# mv-uart.net
KiCad netlist of a schematic drawn in EAGLE
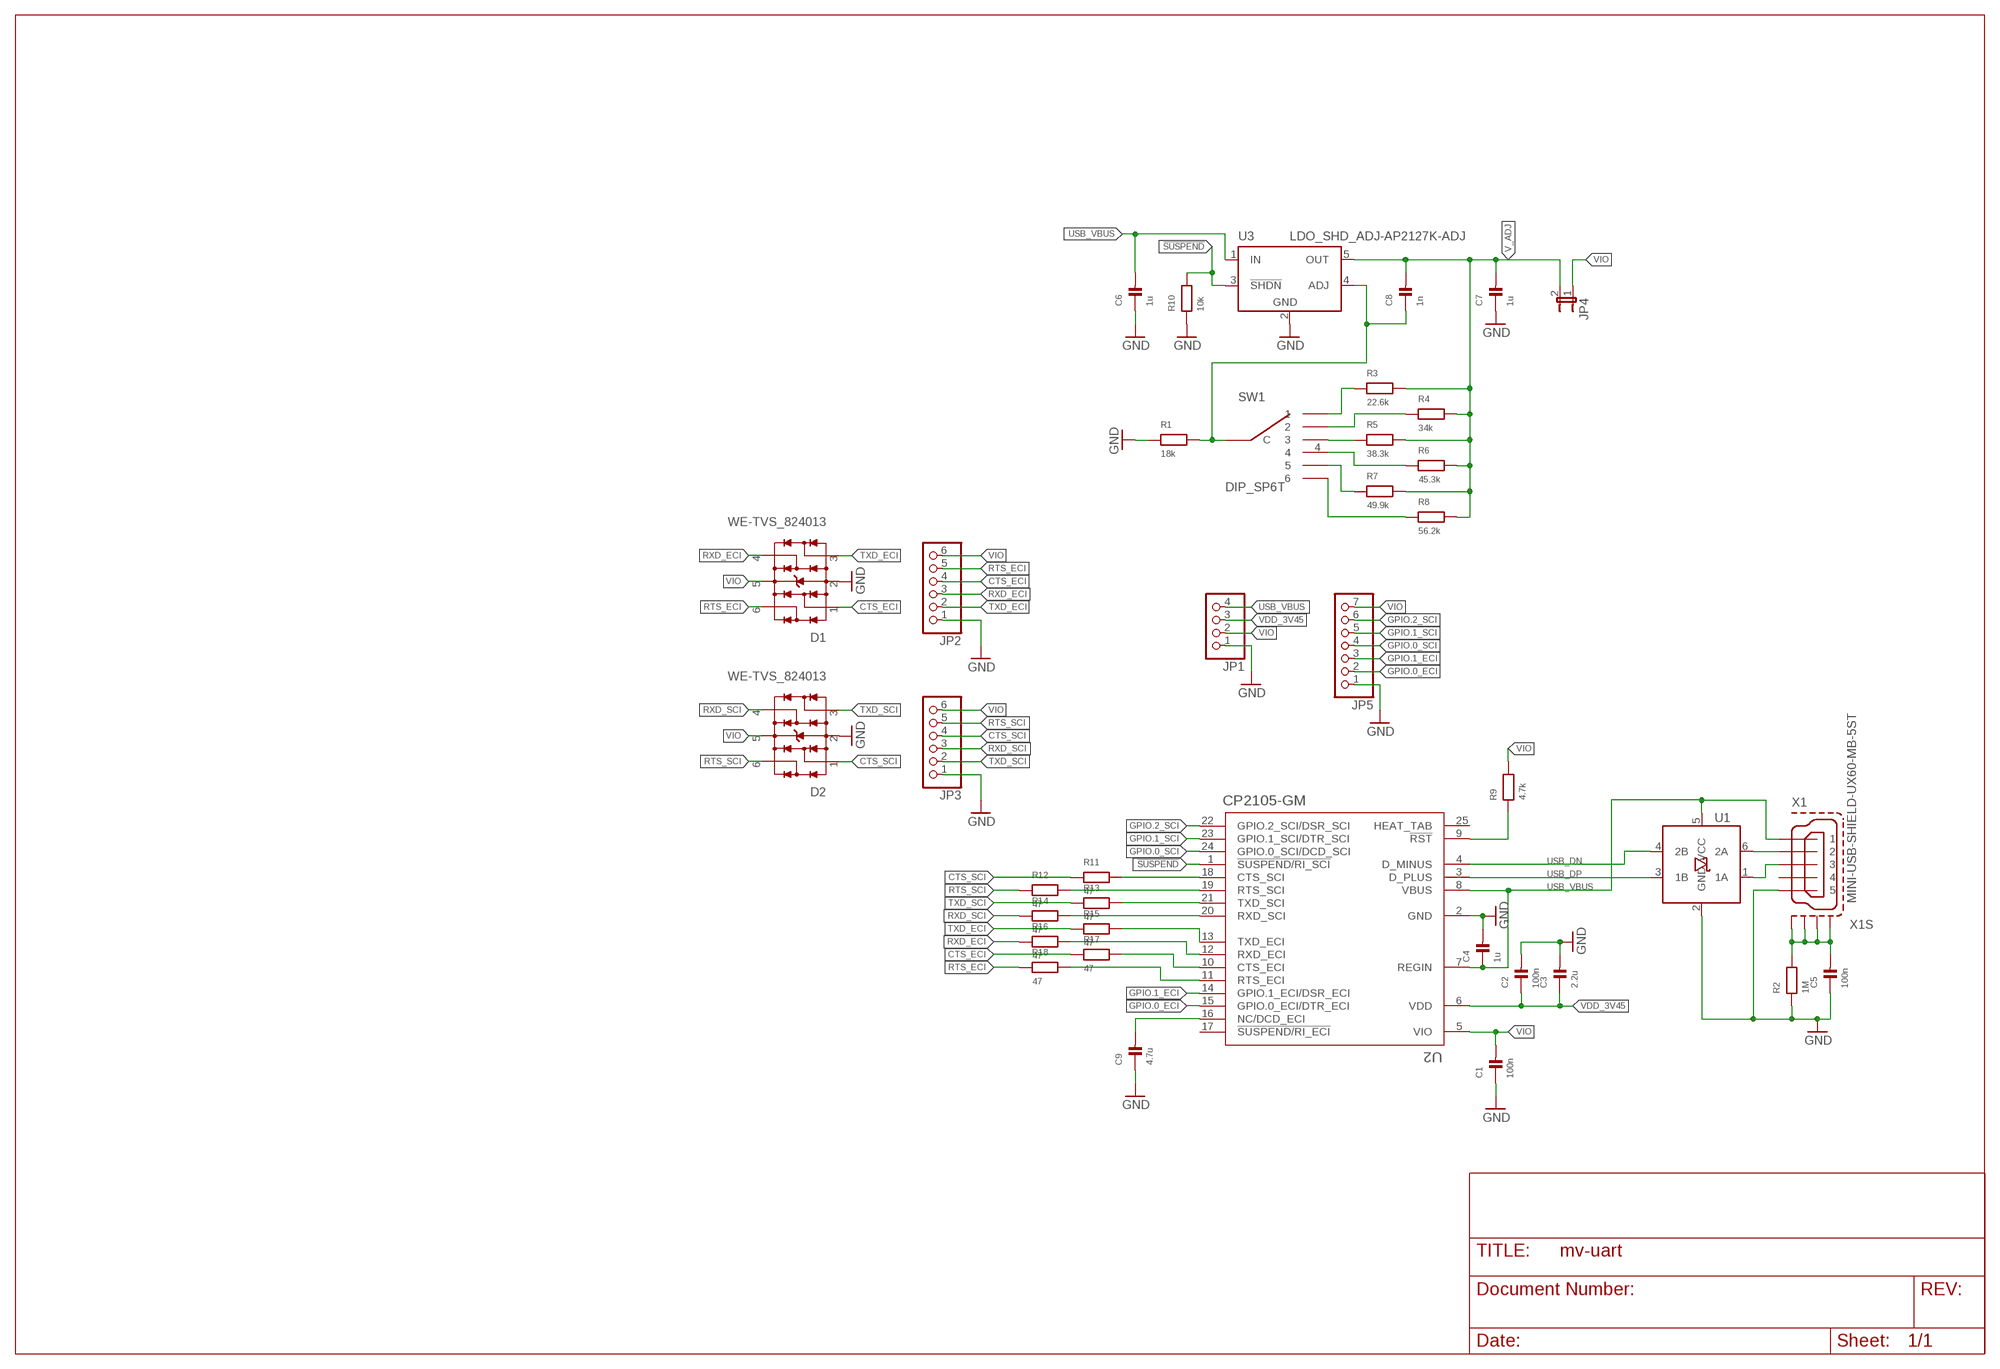
[diagram p0: schematic, sheet 1]

(export (version "E")
  (design (tool "Eeschema 10.0.6"))
  (components
    (comp (ref "C1")
      (value "100n")
      (footprint "eagle-import:_0603")
      (libsource (lib "eagle-import") (part "CAP_CERAMIC_0603"))
    )
    (comp (ref "C2")
      (value "100n")
      (footprint "eagle-import:_0603")
      (libsource (lib "eagle-import") (part "CAP_CERAMIC_0603"))
    )
    (comp (ref "C3")
      (value "2.2u")
      (footprint "eagle-import:_0603")
      (libsource (lib "eagle-import") (part "CAP_CERAMIC_0603"))
    )
    (comp (ref "C4")
      (value "1u")
      (footprint "eagle-import:_0603")
      (libsource (lib "eagle-import") (part "CAP_CERAMIC_0603"))
    )
    (comp (ref "C5")
      (value "100n")
      (footprint "eagle-import:_0603")
      (libsource (lib "eagle-import") (part "CAP_CERAMIC_0603"))
    )
    (comp (ref "C6")
      (value "1u")
      (footprint "eagle-import:_0603")
      (libsource (lib "eagle-import") (part "CAP_CERAMIC_0603"))
    )
    (comp (ref "C7")
      (value "1u")
      (footprint "eagle-import:_0603")
      (libsource (lib "eagle-import") (part "CAP_CERAMIC_0603"))
    )
    (comp (ref "C8")
      (value "1n")
      (footprint "eagle-import:_0603")
      (libsource (lib "eagle-import") (part "CAP_CERAMIC_0603"))
    )
    (comp (ref "C9")
      (value "4.7u")
      (footprint "eagle-import:_0603")
      (libsource (lib "eagle-import") (part "CAP_CERAMIC_0603"))
    )
    (comp (ref "D1")
      (value "WE-TVS_824013")
      (footprint "eagle-import:WE-TVS_SOT23-6L")
      (libsource (lib "eagle-import") (part "WE-TVS_824013"))
    )
    (comp (ref "D2")
      (value "WE-TVS_824013")
      (footprint "eagle-import:WE-TVS_SOT23-6L")
      (libsource (lib "eagle-import") (part "WE-TVS_824013"))
    )
    (comp (ref "JP1")
      (value "PINHD-1X4")
      (footprint "eagle-import:1X04")
      (libsource (lib "eagle-import") (part "PINHD-1X4"))
    )
    (comp (ref "JP2")
      (value "PINHD-1X6/90")
      (footprint "eagle-import:1X06_90")
      (libsource (lib "eagle-import") (part "PINHD-1X6/90"))
    )
    (comp (ref "JP3")
      (value "PINHD-1X6/90")
      (footprint "eagle-import:1X06_90")
      (libsource (lib "eagle-import") (part "PINHD-1X6/90"))
    )
    (comp (ref "JP4")
      (value "JP1E")
      (footprint "eagle-import:JP1")
      (libsource (lib "eagle-import") (part "JP1E"))
    )
    (comp (ref "JP5")
      (value "PINHD-1X7")
      (footprint "eagle-import:1X07")
      (libsource (lib "eagle-import") (part "PINHD-1X7"))
    )
    (comp (ref "R1")
      (value "18k")
      (footprint "eagle-import:_0603")
      (libsource (lib "eagle-import") (part "RESISTOR_0603"))
    )
    (comp (ref "R2")
      (value "1M")
      (footprint "eagle-import:_0603")
      (libsource (lib "eagle-import") (part "RESISTOR_0603"))
    )
    (comp (ref "R3")
      (value "22.6k")
      (footprint "eagle-import:_0603")
      (libsource (lib "eagle-import") (part "RESISTOR_0603"))
    )
    (comp (ref "R4")
      (value "34k")
      (footprint "eagle-import:_0603")
      (libsource (lib "eagle-import") (part "RESISTOR_0603"))
    )
    (comp (ref "R5")
      (value "38.3k")
      (footprint "eagle-import:_0603")
      (libsource (lib "eagle-import") (part "RESISTOR_0603"))
    )
    (comp (ref "R6")
      (value "45.3k")
      (footprint "eagle-import:_0603")
      (libsource (lib "eagle-import") (part "RESISTOR_0603"))
    )
    (comp (ref "R7")
      (value "49.9k")
      (footprint "eagle-import:_0603")
      (libsource (lib "eagle-import") (part "RESISTOR_0603"))
    )
    (comp (ref "R8")
      (value "56.2k")
      (footprint "eagle-import:_0603")
      (libsource (lib "eagle-import") (part "RESISTOR_0603"))
    )
    (comp (ref "R9")
      (value "4.7k")
      (footprint "eagle-import:_0603")
      (libsource (lib "eagle-import") (part "RESISTOR_0603"))
    )
    (comp (ref "R10")
      (value "10k")
      (footprint "eagle-import:_0603")
      (libsource (lib "eagle-import") (part "RESISTOR_0603"))
    )
    (comp (ref "R11")
      (value "47")
      (footprint "eagle-import:_0603")
      (libsource (lib "eagle-import") (part "RESISTOR_0603"))
    )
    (comp (ref "R12")
      (value "47")
      (footprint "eagle-import:_0603")
      (libsource (lib "eagle-import") (part "RESISTOR_0603"))
    )
    (comp (ref "R13")
      (value "47")
      (footprint "eagle-import:_0603")
      (libsource (lib "eagle-import") (part "RESISTOR_0603"))
    )
    (comp (ref "R14")
      (value "47")
      (footprint "eagle-import:_0603")
      (libsource (lib "eagle-import") (part "RESISTOR_0603"))
    )
    (comp (ref "R15")
      (value "47")
      (footprint "eagle-import:_0603")
      (libsource (lib "eagle-import") (part "RESISTOR_0603"))
    )
    (comp (ref "R16")
      (value "47")
      (footprint "eagle-import:_0603")
      (libsource (lib "eagle-import") (part "RESISTOR_0603"))
    )
    (comp (ref "R17")
      (value "47")
      (footprint "eagle-import:_0603")
      (libsource (lib "eagle-import") (part "RESISTOR_0603"))
    )
    (comp (ref "R18")
      (value "47")
      (footprint "eagle-import:_0603")
      (libsource (lib "eagle-import") (part "RESISTOR_0603"))
    )
    (comp (ref "SW1")
      (value "DIP_SP6T")
      (footprint "eagle-import:DIP_SP6T")
      (libsource (lib "eagle-import") (part "DIP_SP6T"))
    )
    (comp (ref "U1")
      (value "IP4234CZ6")
      (footprint "eagle-import:TSOP-6")
      (libsource (lib "eagle-import") (part "IP4234CZ6"))
    )
    (comp (ref "U2")
      (value "CP2105-GM")
      (footprint "eagle-import:QFN24_4X4")
      (libsource (lib "eagle-import") (part "CP2105-GM"))
    )
    (comp (ref "U3")
      (value "LDO_SHD_ADJ-AP2127K-ADJ")
      (footprint "eagle-import:SOT23L")
      (libsource (lib "eagle-import") (part "LDO_SHD_ADJ-AP2127K-ADJ"))
    )
    (comp (ref "X1")
      (value "MINI-USB-SHIELD-UX60-MB-5ST")
      (footprint "eagle-import:UX60-MB-5ST")
      (libsource (lib "eagle-import") (part "MINI-USB-SHIELD-UX60-MB-5ST"))
    )
  )
  (nets
    (net (code "1") (name "/USB_DN") (class "Default")
      (node (ref "U1") (pin "4") (pinfunction "2B_4") (pintype "passive"))
      (node (ref "U2") (pin "4") (pinfunction "D_MINUS_4") (pintype "passive"))
    )
    (net (code "2") (name "/USB_DP") (class "Default")
      (node (ref "U1") (pin "3") (pinfunction "1B_3") (pintype "passive"))
      (node (ref "U2") (pin "3") (pinfunction "D_PLUS_3") (pintype "passive"))
    )
    (net (code "3") (name "/~{SUSPEND}") (class "Default")
      (node (ref "R10") (pin "2") (pinfunction "2_2") (pintype "passive"))
      (node (ref "U2") (pin "1") (pinfunction "~{SUSPEND/RI_SCI}_1") (pintype "passive"))
      (node (ref "U3") (pin "3") (pinfunction "~{SHDN}_3") (pintype "input"))
    )
    (net (code "4") (name "CTS_ECI") (class "Default")
      (node (ref "D1") (pin "1") (pinfunction "1_1") (pintype "passive"))
      (node (ref "JP2") (pin "4") (pinfunction "4_4") (pintype "passive"))
      (node (ref "R17") (pin "1") (pinfunction "1_1") (pintype "passive"))
    )
    (net (code "5") (name "CTS_SCI") (class "Default")
      (node (ref "D2") (pin "1") (pinfunction "1_1") (pintype "passive"))
      (node (ref "JP3") (pin "4") (pinfunction "4_4") (pintype "passive"))
      (node (ref "R11") (pin "1") (pinfunction "1_1") (pintype "passive"))
    )
    (net (code "6") (name "GND") (class "Default")
      (node (ref "C1") (pin "1") (pinfunction "1_1") (pintype "passive"))
      (node (ref "C2") (pin "2") (pinfunction "2_2") (pintype "passive"))
      (node (ref "C3") (pin "2") (pinfunction "2_2") (pintype "passive"))
      (node (ref "C4") (pin "2") (pinfunction "2_2") (pintype "passive"))
      (node (ref "C5") (pin "1") (pinfunction "1_1") (pintype "passive"))
      (node (ref "C6") (pin "1") (pinfunction "1_1") (pintype "passive"))
      (node (ref "C7") (pin "1") (pinfunction "1_1") (pintype "passive"))
      (node (ref "C9") (pin "1") (pinfunction "1_1") (pintype "passive"))
      (node (ref "D1") (pin "2") (pinfunction "GND_2") (pintype "power_in"))
      (node (ref "D2") (pin "2") (pinfunction "GND_2") (pintype "power_in"))
      (node (ref "JP1") (pin "1") (pinfunction "1_1") (pintype "passive"))
      (node (ref "JP2") (pin "1") (pinfunction "1_1") (pintype "passive"))
      (node (ref "JP3") (pin "1") (pinfunction "1_1") (pintype "passive"))
      (node (ref "JP5") (pin "1") (pinfunction "1_1") (pintype "passive"))
      (node (ref "R1") (pin "1") (pinfunction "1_1") (pintype "passive"))
      (node (ref "R10") (pin "1") (pinfunction "1_1") (pintype "passive"))
      (node (ref "R2") (pin "1") (pinfunction "1_1") (pintype "passive"))
      (node (ref "U1") (pin "2") (pinfunction "GND_2") (pintype "passive"))
      (node (ref "U2") (pin "2") (pinfunction "GND_2") (pintype "power_in"))
      (node (ref "U3") (pin "2") (pinfunction "GND_2") (pintype "power_in"))
      (node (ref "X1") (pin "5") (pinfunction "5_5") (pintype "input"))
    )
    (net (code "7") (name "GPIO.0_ECI") (class "Default")
      (node (ref "JP5") (pin "2") (pinfunction "2_2") (pintype "passive"))
      (node (ref "U2") (pin "15") (pinfunction "GPIO.0_ECI/DTR_ECI_15") (pintype "passive"))
    )
    (net (code "8") (name "GPIO.0_SCI") (class "Default")
      (node (ref "JP5") (pin "4") (pinfunction "4_4") (pintype "passive"))
      (node (ref "U2") (pin "24") (pinfunction "GPIO.0_SCI/DCD_SCI_24") (pintype "passive"))
    )
    (net (code "9") (name "GPIO.1_ECI") (class "Default")
      (node (ref "JP5") (pin "3") (pinfunction "3_3") (pintype "passive"))
      (node (ref "U2") (pin "14") (pinfunction "GPIO.1_ECI/DSR_ECI_14") (pintype "passive"))
    )
    (net (code "10") (name "GPIO.1_SCI") (class "Default")
      (node (ref "JP5") (pin "5") (pinfunction "5_5") (pintype "passive"))
      (node (ref "U2") (pin "23") (pinfunction "GPIO.1_SCI/DTR_SCI_23") (pintype "passive"))
    )
    (net (code "11") (name "GPIO.2_SCI") (class "Default")
      (node (ref "JP5") (pin "6") (pinfunction "6_6") (pintype "passive"))
      (node (ref "U2") (pin "22") (pinfunction "GPIO.2_SCI/DSR_SCI_22") (pintype "passive"))
    )
    (net (code "12") (name "Net-(R3-Pad1)") (class "Default")
      (node (ref "R3") (pin "1") (pinfunction "1_1") (pintype "passive"))
      (node (ref "SW1") (pin "1") (pinfunction "1_1") (pintype "bidirectional"))
    )
    (net (code "13") (name "Net-(R4-Pad1)") (class "Default")
      (node (ref "R4") (pin "1") (pinfunction "1_1") (pintype "passive"))
      (node (ref "SW1") (pin "2") (pinfunction "2_2") (pintype "bidirectional"))
    )
    (net (code "14") (name "Net-(R5-Pad1)") (class "Default")
      (node (ref "R5") (pin "1") (pinfunction "1_1") (pintype "passive"))
      (node (ref "SW1") (pin "3") (pinfunction "3_3") (pintype "bidirectional"))
    )
    (net (code "15") (name "Net-(R6-Pad1)") (class "Default")
      (node (ref "R6") (pin "1") (pinfunction "1_1") (pintype "passive"))
      (node (ref "SW1") (pin "4") (pinfunction "4_4") (pintype "bidirectional"))
    )
    (net (code "16") (name "Net-(R7-Pad1)") (class "Default")
      (node (ref "R7") (pin "1") (pinfunction "1_1") (pintype "passive"))
      (node (ref "SW1") (pin "5") (pinfunction "5_5") (pintype "bidirectional"))
    )
    (net (code "17") (name "Net-(R8-Pad1)") (class "Default")
      (node (ref "R8") (pin "1") (pinfunction "1_1") (pintype "passive"))
      (node (ref "SW1") (pin "6") (pinfunction "6_6") (pintype "bidirectional"))
    )
    (net (code "18") (name "Net-(U1-1A)") (class "Default")
      (node (ref "U1") (pin "1") (pinfunction "1A_1") (pintype "passive"))
      (node (ref "X1") (pin "3") (pinfunction "3_3") (pintype "input"))
    )
    (net (code "19") (name "Net-(U1-2A)") (class "Default")
      (node (ref "U1") (pin "6") (pinfunction "2A_6") (pintype "passive"))
      (node (ref "X1") (pin "2") (pinfunction "2_2") (pintype "input"))
    )
    (net (code "20") (name "Net-(U2-CTS_ECI)") (class "Default")
      (node (ref "R17") (pin "2") (pinfunction "2_2") (pintype "passive"))
      (node (ref "U2") (pin "10") (pinfunction "CTS_ECI_10") (pintype "passive"))
    )
    (net (code "21") (name "Net-(U2-CTS_SCI)") (class "Default")
      (node (ref "R11") (pin "2") (pinfunction "2_2") (pintype "passive"))
      (node (ref "U2") (pin "18") (pinfunction "CTS_SCI_18") (pintype "passive"))
    )
    (net (code "22") (name "Net-(U2-NC{slash}DCD_ECI)") (class "Default")
      (node (ref "C9") (pin "2") (pinfunction "2_2") (pintype "passive"))
      (node (ref "U2") (pin "16") (pinfunction "NC/DCD_ECI_16") (pintype "passive"))
    )
    (net (code "23") (name "Net-(U2-RTS_ECI)") (class "Default")
      (node (ref "R18") (pin "2") (pinfunction "2_2") (pintype "passive"))
      (node (ref "U2") (pin "11") (pinfunction "RTS_ECI_11") (pintype "passive"))
    )
    (net (code "24") (name "Net-(U2-RTS_SCI)") (class "Default")
      (node (ref "R12") (pin "2") (pinfunction "2_2") (pintype "passive"))
      (node (ref "U2") (pin "19") (pinfunction "RTS_SCI_19") (pintype "passive"))
    )
    (net (code "25") (name "Net-(U2-RXD_ECI)") (class "Default")
      (node (ref "R16") (pin "2") (pinfunction "2_2") (pintype "passive"))
      (node (ref "U2") (pin "12") (pinfunction "RXD_ECI_12") (pintype "passive"))
    )
    (net (code "26") (name "Net-(U2-RXD_SCI)") (class "Default")
      (node (ref "R14") (pin "2") (pinfunction "2_2") (pintype "passive"))
      (node (ref "U2") (pin "20") (pinfunction "RXD_SCI_20") (pintype "passive"))
    )
    (net (code "27") (name "Net-(U2-TXD_ECI)") (class "Default")
      (node (ref "R15") (pin "2") (pinfunction "2_2") (pintype "passive"))
      (node (ref "U2") (pin "13") (pinfunction "TXD_ECI_13") (pintype "passive"))
    )
    (net (code "28") (name "Net-(U2-TXD_SCI)") (class "Default")
      (node (ref "R13") (pin "2") (pinfunction "2_2") (pintype "passive"))
      (node (ref "U2") (pin "21") (pinfunction "TXD_SCI_21") (pintype "passive"))
    )
    (net (code "29") (name "Net-(U2-~{RST})") (class "Default")
      (node (ref "R9") (pin "1") (pinfunction "1_1") (pintype "passive"))
      (node (ref "U2") (pin "9") (pinfunction "~{RST}_9") (pintype "passive"))
    )
    (net (code "30") (name "Net-(U3-ADJ)") (class "Default")
      (node (ref "C8") (pin "1") (pinfunction "1_1") (pintype "passive"))
      (node (ref "R1") (pin "2") (pinfunction "2_2") (pintype "passive"))
      (node (ref "SW1") (pin "C") (pinfunction "C_C") (pintype "bidirectional"))
      (node (ref "U3") (pin "4") (pinfunction "ADJ_4") (pintype "passive"))
    )
    (net (code "31") (name "Net-(X1B-S1)") (class "Default")
      (node (ref "C5") (pin "2") (pinfunction "2_2") (pintype "passive"))
      (node (ref "R2") (pin "2") (pinfunction "2_2") (pintype "passive"))
      (node (ref "X1") (pin "M1") (pinfunction "S1_M1") (pintype "passive"))
      (node (ref "X1") (pin "M2") (pinfunction "S2_M2") (pintype "passive"))
      (node (ref "X1") (pin "M3") (pinfunction "S3_M3") (pintype "passive"))
      (node (ref "X1") (pin "M4") (pinfunction "S4_M4") (pintype "passive"))
    )
    (net (code "32") (name "RTS_ECI") (class "Default")
      (node (ref "D1") (pin "6") (pinfunction "4_6") (pintype "passive"))
      (node (ref "JP2") (pin "5") (pinfunction "5_5") (pintype "passive"))
      (node (ref "R18") (pin "1") (pinfunction "1_1") (pintype "passive"))
    )
    (net (code "33") (name "RTS_SCI") (class "Default")
      (node (ref "D2") (pin "6") (pinfunction "4_6") (pintype "passive"))
      (node (ref "JP3") (pin "5") (pinfunction "5_5") (pintype "passive"))
      (node (ref "R12") (pin "1") (pinfunction "1_1") (pintype "passive"))
    )
    (net (code "34") (name "RXD_ECI") (class "Default")
      (node (ref "D1") (pin "4") (pinfunction "3_4") (pintype "passive"))
      (node (ref "JP2") (pin "3") (pinfunction "3_3") (pintype "passive"))
      (node (ref "R16") (pin "1") (pinfunction "1_1") (pintype "passive"))
    )
    (net (code "35") (name "RXD_SCI") (class "Default")
      (node (ref "D2") (pin "4") (pinfunction "3_4") (pintype "passive"))
      (node (ref "JP3") (pin "3") (pinfunction "3_3") (pintype "passive"))
      (node (ref "R14") (pin "1") (pinfunction "1_1") (pintype "passive"))
    )
    (net (code "36") (name "TXD_ECI") (class "Default")
      (node (ref "D1") (pin "3") (pinfunction "2_3") (pintype "passive"))
      (node (ref "JP2") (pin "2") (pinfunction "2_2") (pintype "passive"))
      (node (ref "R15") (pin "1") (pinfunction "1_1") (pintype "passive"))
    )
    (net (code "37") (name "TXD_SCI") (class "Default")
      (node (ref "D2") (pin "3") (pinfunction "2_3") (pintype "passive"))
      (node (ref "JP3") (pin "2") (pinfunction "2_2") (pintype "passive"))
      (node (ref "R13") (pin "1") (pinfunction "1_1") (pintype "passive"))
    )
    (net (code "38") (name "USB_VBUS") (class "Default")
      (node (ref "C4") (pin "1") (pinfunction "1_1") (pintype "passive"))
      (node (ref "C6") (pin "2") (pinfunction "2_2") (pintype "passive"))
      (node (ref "JP1") (pin "4") (pinfunction "4_4") (pintype "passive"))
      (node (ref "U1") (pin "5") (pinfunction "VCC_5") (pintype "passive"))
      (node (ref "U2") (pin "7") (pinfunction "REGIN_7") (pintype "input"))
      (node (ref "U2") (pin "8") (pinfunction "VBUS_8") (pintype "input"))
      (node (ref "U3") (pin "1") (pinfunction "IN_1") (pintype "input"))
      (node (ref "X1") (pin "1") (pinfunction "1_1") (pintype "input"))
    )
    (net (code "39") (name "VDD_3V45") (class "Default")
      (node (ref "C2") (pin "1") (pinfunction "1_1") (pintype "passive"))
      (node (ref "C3") (pin "1") (pinfunction "1_1") (pintype "passive"))
      (node (ref "JP1") (pin "3") (pinfunction "3_3") (pintype "passive"))
      (node (ref "U2") (pin "6") (pinfunction "VDD_6") (pintype "power_in"))
    )
    (net (code "40") (name "VIO") (class "Default")
      (node (ref "C1") (pin "2") (pinfunction "2_2") (pintype "passive"))
      (node (ref "D1") (pin "5") (pinfunction "VDD_5") (pintype "power_in"))
      (node (ref "D2") (pin "5") (pinfunction "VDD_5") (pintype "power_in"))
      (node (ref "JP1") (pin "2") (pinfunction "2_2") (pintype "passive"))
      (node (ref "JP2") (pin "6") (pinfunction "6_6") (pintype "passive"))
      (node (ref "JP3") (pin "6") (pinfunction "6_6") (pintype "passive"))
      (node (ref "JP4") (pin "1") (pinfunction "1_1") (pintype "passive"))
      (node (ref "JP5") (pin "7") (pinfunction "7_7") (pintype "passive"))
      (node (ref "R9") (pin "2") (pinfunction "2_2") (pintype "passive"))
      (node (ref "U2") (pin "5") (pinfunction "VIO_5") (pintype "power_in"))
    )
    (net (code "41") (name "V_ADJ") (class "Default")
      (node (ref "C7") (pin "2") (pinfunction "2_2") (pintype "passive"))
      (node (ref "C8") (pin "2") (pinfunction "2_2") (pintype "passive"))
      (node (ref "JP4") (pin "2") (pinfunction "2_2") (pintype "passive"))
      (node (ref "R3") (pin "2") (pinfunction "2_2") (pintype "passive"))
      (node (ref "R4") (pin "2") (pinfunction "2_2") (pintype "passive"))
      (node (ref "R5") (pin "2") (pinfunction "2_2") (pintype "passive"))
      (node (ref "R6") (pin "2") (pinfunction "2_2") (pintype "passive"))
      (node (ref "R7") (pin "2") (pinfunction "2_2") (pintype "passive"))
      (node (ref "R8") (pin "2") (pinfunction "2_2") (pintype "passive"))
      (node (ref "U3") (pin "5") (pinfunction "OUT_5") (pintype "passive"))
    )
    (net (code "42") (name "unconnected-(U2-HEAT_TAB-Pad25)") (class "Default")
      (node (ref "U2") (pin "25") (pinfunction "HEAT_TAB_25") (pintype "passive"))
    )
    (net (code "43") (name "unconnected-(U2-~{SUSPEND{slash}RI_ECI}-Pad17)") (class "Default")
      (node (ref "U2") (pin "17") (pinfunction "~{SUSPEND/RI_ECI}_17") (pintype "passive"))
    )
    (net (code "44") (name "unconnected-(X1-Pad4)") (class "Default")
      (node (ref "X1") (pin "4") (pinfunction "4_4") (pintype "input"))
    )
  )
)
